# SMDschemtatic.net
KiCad netlist of a schematic drawn in EAGLE
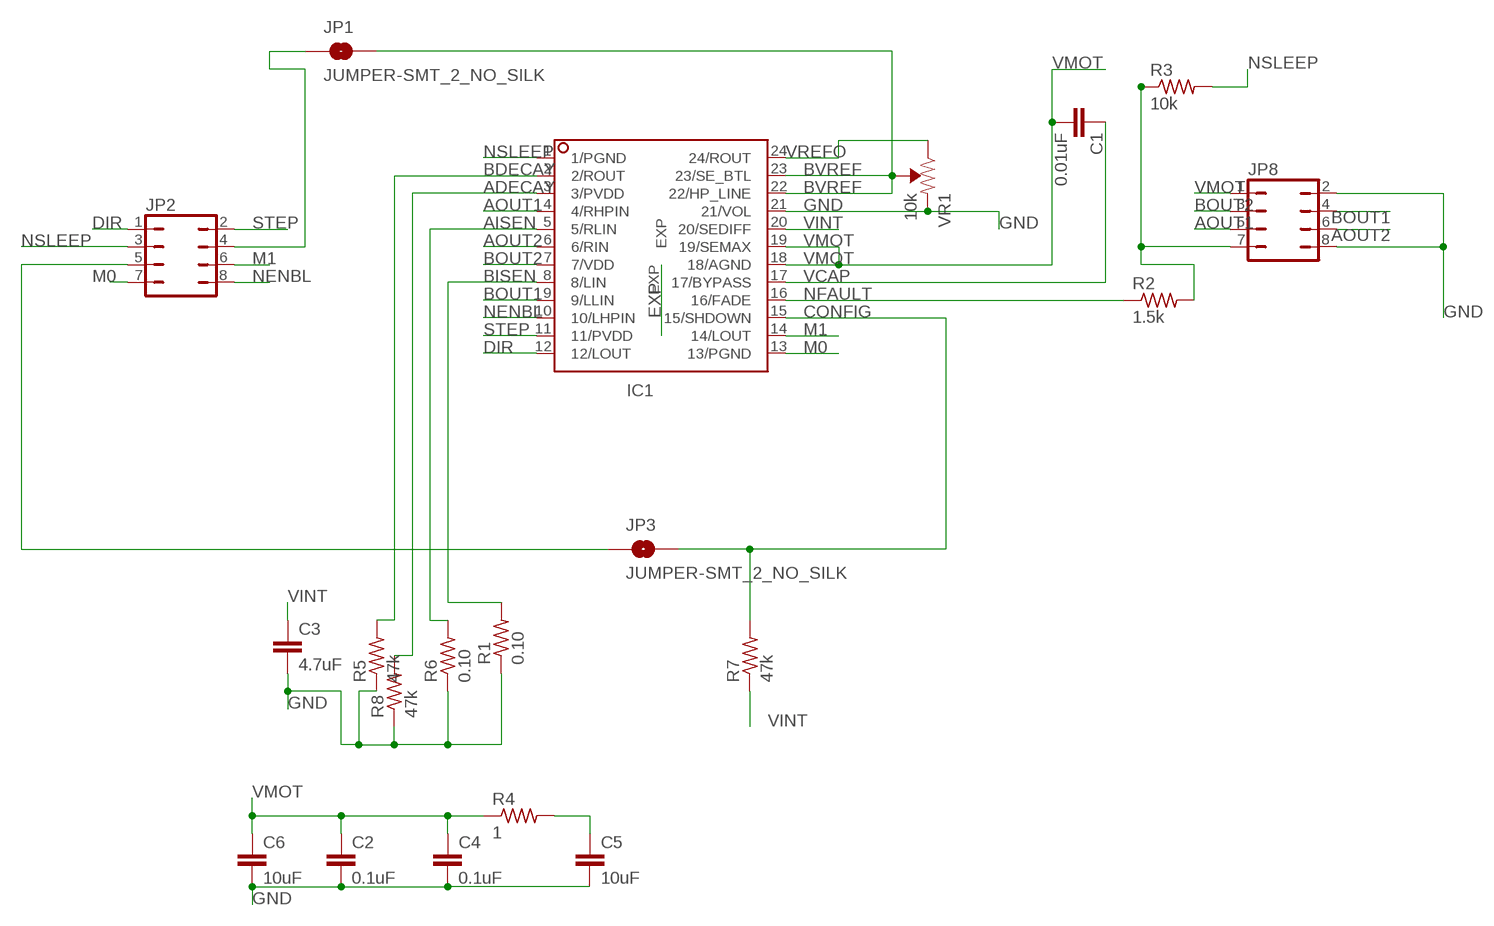
[diagram p0: schematic, sheet 1]

(export (version "E")
  (design (tool "Eeschema 10.0.6"))
  (components
    (comp (ref "C1")
      (value "0.01uF")
      (footprint "eagle-import:0603")
      (libsource (lib "eagle-import") (part "10NF-0603-50V-10%"))
    )
    (comp (ref "C2")
      (value "0.1uF")
      (footprint "eagle-import:0603")
      (libsource (lib "eagle-import") (part "10NF-0603-50V-10%"))
    )
    (comp (ref "C3")
      (value "4.7uF")
      (footprint "eagle-import:0603")
      (libsource (lib "eagle-import") (part "10NF-0603-50V-10%"))
    )
    (comp (ref "C4")
      (value "0.1uF")
      (footprint "eagle-import:0603")
      (libsource (lib "eagle-import") (part "10NF-0603-50V-10%"))
    )
    (comp (ref "C5")
      (value "10uF")
      (footprint "eagle-import:0603")
      (libsource (lib "eagle-import") (part "10NF-0603-50V-10%"))
    )
    (comp (ref "C6")
      (value "10uF")
      (footprint "eagle-import:0603")
      (libsource (lib "eagle-import") (part "10NF-0603-50V-10%"))
    )
    (comp (ref "IC1")
      (value "PA3011")
      (footprint "eagle-import:HTSSOP24")
      (libsource (lib "eagle-import") (part "PA3011"))
    )
    (comp (ref "JP1")
      (value "JUMPER-SMT_2_NO_SILK")
      (footprint "eagle-import:SMT-JUMPER_2_NO_SILK")
      (libsource (lib "eagle-import") (part "JUMPER-SMT_2_NO_SILK"))
    )
    (comp (ref "JP2")
      (value "JP4Q")
      (footprint "eagle-import:JP4Q")
      (libsource (lib "eagle-import") (part "JP4Q"))
    )
    (comp (ref "JP3")
      (value "JUMPER-SMT_2_NO_SILK")
      (footprint "eagle-import:SMT-JUMPER_2_NO_SILK")
      (libsource (lib "eagle-import") (part "JUMPER-SMT_2_NO_SILK"))
    )
    (comp (ref "JP8")
      (value "JP4Q")
      (footprint "eagle-import:JP4Q")
      (libsource (lib "eagle-import") (part "JP4Q"))
    )
    (comp (ref "R1")
      (value "0.10")
      (footprint "eagle-import:R2512")
      (libsource (lib "eagle-import") (part "R-US_R2512"))
    )
    (comp (ref "R2")
      (value "1.5k")
      (footprint "eagle-import:R2512")
      (libsource (lib "eagle-import") (part "R-US_R2512"))
    )
    (comp (ref "R3")
      (value "10k")
      (footprint "eagle-import:R2512")
      (libsource (lib "eagle-import") (part "R-US_R2512"))
    )
    (comp (ref "R4")
      (value "1")
      (footprint "eagle-import:R2512")
      (libsource (lib "eagle-import") (part "R-US_R2512"))
    )
    (comp (ref "R5")
      (value "47k")
      (footprint "eagle-import:R2512")
      (libsource (lib "eagle-import") (part "R-US_R2512"))
    )
    (comp (ref "R6")
      (value "0.10")
      (footprint "eagle-import:R2512")
      (libsource (lib "eagle-import") (part "R-US_R2512"))
    )
    (comp (ref "R7")
      (value "47k")
      (footprint "eagle-import:R2512")
      (libsource (lib "eagle-import") (part "R-US_R2512"))
    )
    (comp (ref "R8")
      (value "47k")
      (footprint "eagle-import:R2512")
      (libsource (lib "eagle-import") (part "R-US_R2512"))
    )
    (comp (ref "VR1")
      (value "10k")
      (footprint "eagle-import:TRIMPOT-SMD-3MM-CLOSED")
      (libsource (lib "eagle-import") (part "TRIMPOT-SMD-3MM-CLOSED-1/8W-20%"))
    )
  )
  (nets
    (net (code "1") (name "/ADECAY") (class "Default")
      (node (ref "IC1") (pin "3") (pinfunction "3/PVDD_3") (pintype "bidirectional"))
      (node (ref "R8") (pin "2") (pinfunction "2_2") (pintype "passive"))
    )
    (net (code "2") (name "/AISEN") (class "Default")
      (node (ref "IC1") (pin "5") (pinfunction "5/RLIN_5") (pintype "bidirectional"))
      (node (ref "R6") (pin "2") (pinfunction "2_2") (pintype "passive"))
    )
    (net (code "3") (name "/AOUT1") (class "Default")
      (node (ref "IC1") (pin "4") (pinfunction "4/RHPIN_4") (pintype "bidirectional"))
      (node (ref "JP8") (pin "5") (pinfunction "5_5") (pintype "passive"))
    )
    (net (code "4") (name "/AOUT2") (class "Default")
      (node (ref "IC1") (pin "6") (pinfunction "6/RIN_6") (pintype "bidirectional"))
      (node (ref "JP8") (pin "6") (pinfunction "6_6") (pintype "passive"))
    )
    (net (code "5") (name "/BDECAY") (class "Default")
      (node (ref "IC1") (pin "2") (pinfunction "2/ROUT_2") (pintype "bidirectional"))
      (node (ref "R5") (pin "2") (pinfunction "2_2") (pintype "passive"))
    )
    (net (code "6") (name "/BISEN") (class "Default")
      (node (ref "IC1") (pin "8") (pinfunction "8/LIN_8") (pintype "bidirectional"))
      (node (ref "R1") (pin "2") (pinfunction "2_2") (pintype "passive"))
    )
    (net (code "7") (name "/BOUT1") (class "Default")
      (node (ref "IC1") (pin "9") (pinfunction "9/LLIN_9") (pintype "bidirectional"))
      (node (ref "JP8") (pin "4") (pinfunction "4_4") (pintype "passive"))
    )
    (net (code "8") (name "/BOUT2") (class "Default")
      (node (ref "IC1") (pin "7") (pinfunction "7/VDD_7") (pintype "bidirectional"))
      (node (ref "JP8") (pin "3") (pinfunction "3_3") (pintype "passive"))
    )
    (net (code "9") (name "/BVREF") (class "Default")
      (node (ref "IC1") (pin "22") (pinfunction "22/HP_LINE_22") (pintype "bidirectional"))
      (node (ref "IC1") (pin "23") (pinfunction "23/SE_BTL_23") (pintype "bidirectional"))
      (node (ref "JP1") (pin "2") (pinfunction "2_2") (pintype "passive"))
      (node (ref "VR1") (pin "2") (pinfunction "WIPER_2") (pintype "passive"))
    )
    (net (code "10") (name "/CONFIG") (class "Default")
      (node (ref "IC1") (pin "15") (pinfunction "15/SHDOWN_15") (pintype "bidirectional"))
      (node (ref "JP3") (pin "2") (pinfunction "2_2") (pintype "passive"))
      (node (ref "R7") (pin "2") (pinfunction "2_2") (pintype "passive"))
    )
    (net (code "11") (name "/DIR") (class "Default")
      (node (ref "IC1") (pin "12") (pinfunction "12/LOUT_12") (pintype "bidirectional"))
      (node (ref "JP2") (pin "1") (pinfunction "1_1") (pintype "passive"))
    )
    (net (code "12") (name "/EXP") (class "Default")
      (node (ref "IC1") (pin "EXP") (pinfunction "EXP_EXP") (pintype "bidirectional"))
    )
    (net (code "13") (name "/GND") (class "Default")
      (node (ref "C2") (pin "2") (pinfunction "2_2") (pintype "passive"))
      (node (ref "C3") (pin "2") (pinfunction "2_2") (pintype "passive"))
      (node (ref "C4") (pin "2") (pinfunction "2_2") (pintype "passive"))
      (node (ref "C5") (pin "2") (pinfunction "2_2") (pintype "passive"))
      (node (ref "C6") (pin "2") (pinfunction "2_2") (pintype "passive"))
      (node (ref "IC1") (pin "21") (pinfunction "21/VOL_21") (pintype "bidirectional"))
      (node (ref "JP8") (pin "2") (pinfunction "2_2") (pintype "passive"))
      (node (ref "JP8") (pin "8") (pinfunction "8_8") (pintype "passive"))
      (node (ref "R1") (pin "1") (pinfunction "1_1") (pintype "passive"))
      (node (ref "R5") (pin "1") (pinfunction "1_1") (pintype "passive"))
      (node (ref "R6") (pin "1") (pinfunction "1_1") (pintype "passive"))
      (node (ref "R8") (pin "1") (pinfunction "1_1") (pintype "passive"))
      (node (ref "VR1") (pin "1") (pinfunction "CCW_1") (pintype "passive"))
    )
    (net (code "14") (name "/M0") (class "Default")
      (node (ref "IC1") (pin "13") (pinfunction "13/PGND_13") (pintype "bidirectional"))
      (node (ref "JP2") (pin "7") (pinfunction "7_7") (pintype "passive"))
    )
    (net (code "15") (name "/M1") (class "Default")
      (node (ref "IC1") (pin "14") (pinfunction "14/LOUT_14") (pintype "bidirectional"))
      (node (ref "JP2") (pin "6") (pinfunction "6_6") (pintype "passive"))
    )
    (net (code "16") (name "/NENBL") (class "Default")
      (node (ref "IC1") (pin "10") (pinfunction "10/LHPIN_10") (pintype "bidirectional"))
      (node (ref "JP2") (pin "8") (pinfunction "8_8") (pintype "passive"))
    )
    (net (code "17") (name "/NFAULT") (class "Default")
      (node (ref "IC1") (pin "16") (pinfunction "16/FADE_16") (pintype "bidirectional"))
      (node (ref "R2") (pin "1") (pinfunction "1_1") (pintype "passive"))
    )
    (net (code "18") (name "/NSLEEP") (class "Default")
      (node (ref "IC1") (pin "1") (pinfunction "1/PGND_1") (pintype "bidirectional"))
      (node (ref "JP2") (pin "3") (pinfunction "3_3") (pintype "passive"))
      (node (ref "R3") (pin "2") (pinfunction "2_2") (pintype "passive"))
    )
    (net (code "19") (name "/STEP") (class "Default")
      (node (ref "IC1") (pin "11") (pinfunction "11/PVDD_11") (pintype "bidirectional"))
      (node (ref "JP2") (pin "2") (pinfunction "2_2") (pintype "passive"))
    )
    (net (code "20") (name "/VCAP") (class "Default")
      (node (ref "C1") (pin "1") (pinfunction "1_1") (pintype "passive"))
      (node (ref "IC1") (pin "17") (pinfunction "17/BYPASS_17") (pintype "bidirectional"))
    )
    (net (code "21") (name "/VINT") (class "Default")
      (node (ref "C3") (pin "1") (pinfunction "1_1") (pintype "passive"))
      (node (ref "IC1") (pin "20") (pinfunction "20/SEDIFF_20") (pintype "bidirectional"))
      (node (ref "R7") (pin "1") (pinfunction "1_1") (pintype "passive"))
    )
    (net (code "22") (name "/VMOT") (class "Default")
      (node (ref "C1") (pin "2") (pinfunction "2_2") (pintype "passive"))
      (node (ref "C2") (pin "1") (pinfunction "1_1") (pintype "passive"))
      (node (ref "C4") (pin "1") (pinfunction "1_1") (pintype "passive"))
      (node (ref "C6") (pin "1") (pinfunction "1_1") (pintype "passive"))
      (node (ref "IC1") (pin "18") (pinfunction "18/AGND_18") (pintype "bidirectional"))
      (node (ref "IC1") (pin "19") (pinfunction "19/SEMAX_19") (pintype "bidirectional"))
      (node (ref "JP8") (pin "1") (pinfunction "1_1") (pintype "passive"))
      (node (ref "R4") (pin "1") (pinfunction "1_1") (pintype "passive"))
    )
    (net (code "23") (name "/VREFO") (class "Default")
      (node (ref "IC1") (pin "24") (pinfunction "24/ROUT_24") (pintype "bidirectional"))
      (node (ref "VR1") (pin "3") (pinfunction "CW_3") (pintype "passive"))
    )
    (net (code "24") (name "Net-(C5-Pad1)") (class "Default")
      (node (ref "C5") (pin "1") (pinfunction "1_1") (pintype "passive"))
      (node (ref "R4") (pin "2") (pinfunction "2_2") (pintype "passive"))
    )
    (net (code "25") (name "Net-(JP1-Pad1)") (class "Default")
      (node (ref "JP1") (pin "1") (pinfunction "1_1") (pintype "passive"))
      (node (ref "JP2") (pin "4") (pinfunction "4_4") (pintype "passive"))
    )
    (net (code "26") (name "Net-(JP2-Pad5)") (class "Default")
      (node (ref "JP2") (pin "5") (pinfunction "5_5") (pintype "passive"))
      (node (ref "JP3") (pin "1") (pinfunction "1_1") (pintype "passive"))
    )
    (net (code "27") (name "Net-(JP8-Pad7)") (class "Default")
      (node (ref "JP8") (pin "7") (pinfunction "7_7") (pintype "passive"))
      (node (ref "R2") (pin "2") (pinfunction "2_2") (pintype "passive"))
      (node (ref "R3") (pin "1") (pinfunction "1_1") (pintype "passive"))
    )
  )
)
